# breakout_tester_1_0.net
KiCad netlist of a schematic drawn in EAGLE
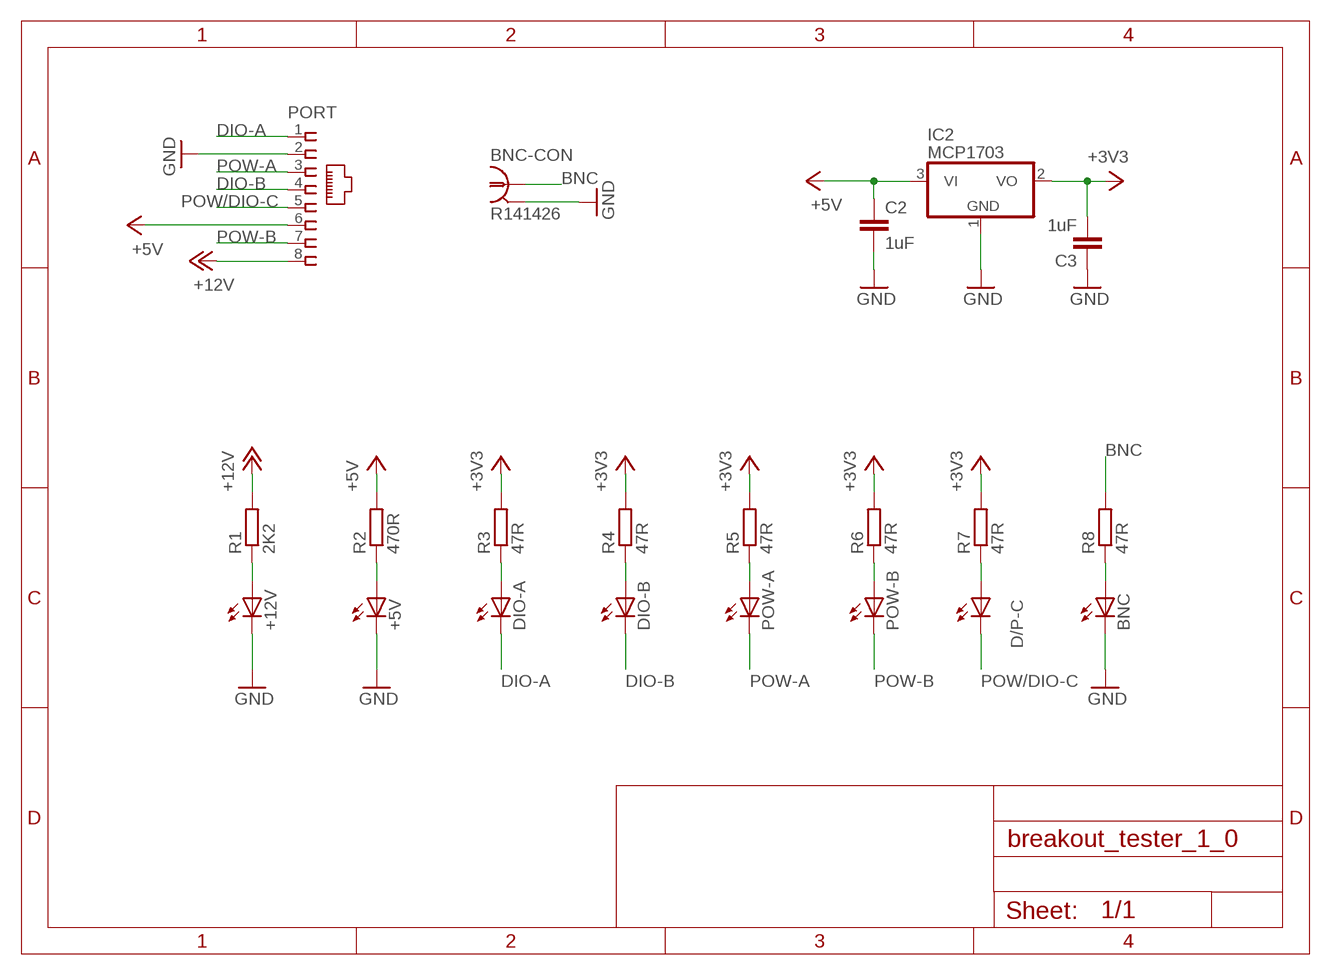
[diagram p0: schematic, sheet 1]

(export (version "E")
  (design (tool "Eeschema 10.0.6"))
  (components
    (comp (ref "+5V")
      (value "LEDSML0805")
      (footprint "eagle-import:SML0805")
      (libsource (lib "eagle-import") (part "LEDSML0805"))
    )
    (comp (ref "+12V")
      (value "LEDSML0805")
      (footprint "eagle-import:SML0805")
      (libsource (lib "eagle-import") (part "LEDSML0805"))
    )
    (comp (ref "BNC")
      (value "LEDSML0805")
      (footprint "eagle-import:SML0805")
      (libsource (lib "eagle-import") (part "LEDSML0805"))
    )
    (comp (ref "BNC-CON")
      (value "R141426")
      (footprint "eagle-import:R141426")
      (fields (field (name "MF") "FARNELL") (field (name "MPN") "R141426161"))
      (libsource (lib "eagle-import") (part "R141426"))
    )
    (comp (ref "C2")
      (value "1uF")
      (footprint "eagle-import:C0805")
      (libsource (lib "eagle-import") (part "resistor_C-EUC0805"))
    )
    (comp (ref "C3")
      (value "1uF")
      (footprint "eagle-import:C0805")
      (libsource (lib "eagle-import") (part "C-EUC0805"))
    )
    (comp (ref "D/P-C")
      (value "LEDSML0805")
      (footprint "eagle-import:SML0805")
      (libsource (lib "eagle-import") (part "LEDSML0805"))
    )
    (comp (ref "DIO-A")
      (value "LEDSML0805")
      (footprint "eagle-import:SML0805")
      (libsource (lib "eagle-import") (part "LEDSML0805"))
    )
    (comp (ref "DIO-B")
      (value "LEDSML0805")
      (footprint "eagle-import:SML0805")
      (libsource (lib "eagle-import") (part "LEDSML0805"))
    )
    (comp (ref "IC2")
      (value "MCP1703")
      (footprint "eagle-import:SOT23")
      (libsource (lib "eagle-import") (part "MCP1703CB"))
    )
    (comp (ref "PORT")
      (value "RJ45VERTICAL")
      (footprint "eagle-import:RJ45-NO-SHIELD-VERTICAL")
      (libsource (lib "eagle-import") (part "RJ45VERTICAL"))
    )
    (comp (ref "POW-A")
      (value "LEDSML0805")
      (footprint "eagle-import:SML0805")
      (libsource (lib "eagle-import") (part "LEDSML0805"))
    )
    (comp (ref "POW-B")
      (value "LEDSML0805")
      (footprint "eagle-import:SML0805")
      (libsource (lib "eagle-import") (part "LEDSML0805"))
    )
    (comp (ref "R1")
      (value "2K2")
      (footprint "eagle-import:M0805")
      (libsource (lib "eagle-import") (part "R-EU_M0805"))
    )
    (comp (ref "R2")
      (value "470R")
      (footprint "eagle-import:M0805")
      (libsource (lib "eagle-import") (part "R-EU_M0805"))
    )
    (comp (ref "R3")
      (value "47R")
      (footprint "eagle-import:M0805")
      (libsource (lib "eagle-import") (part "R-EU_M0805"))
    )
    (comp (ref "R4")
      (value "47R")
      (footprint "eagle-import:M0805")
      (libsource (lib "eagle-import") (part "R-EU_M0805"))
    )
    (comp (ref "R5")
      (value "47R")
      (footprint "eagle-import:M0805")
      (libsource (lib "eagle-import") (part "R-EU_M0805"))
    )
    (comp (ref "R6")
      (value "47R")
      (footprint "eagle-import:M0805")
      (libsource (lib "eagle-import") (part "R-EU_M0805"))
    )
    (comp (ref "R7")
      (value "47R")
      (footprint "eagle-import:M0805")
      (libsource (lib "eagle-import") (part "R-EU_M0805"))
    )
    (comp (ref "R8")
      (value "47R")
      (footprint "eagle-import:M0805")
      (libsource (lib "eagle-import") (part "R-EU_M0805"))
    )
  )
  (nets
    (net (code "1") (name "+3V3") (class "Default")
      (node (ref "C3") (pin "2") (pinfunction "2_2") (pintype "passive"))
      (node (ref "IC2") (pin "2") (pinfunction "VO_2") (pintype "passive"))
      (node (ref "R3") (pin "2") (pinfunction "2_2") (pintype "passive"))
      (node (ref "R4") (pin "2") (pinfunction "2_2") (pintype "passive"))
      (node (ref "R5") (pin "2") (pinfunction "2_2") (pintype "passive"))
      (node (ref "R6") (pin "2") (pinfunction "2_2") (pintype "passive"))
      (node (ref "R7") (pin "2") (pinfunction "2_2") (pintype "passive"))
    )
    (net (code "2") (name "+5V") (class "Default")
      (node (ref "C2") (pin "1") (pinfunction "1_1") (pintype "passive"))
      (node (ref "IC2") (pin "3") (pinfunction "VI_3") (pintype "input"))
      (node (ref "PORT") (pin "6") (pinfunction "6_6") (pintype "passive"))
      (node (ref "R2") (pin "2") (pinfunction "2_2") (pintype "passive"))
    )
    (net (code "3") (name "+12V") (class "Default")
      (node (ref "PORT") (pin "8") (pinfunction "8_8") (pintype "passive"))
      (node (ref "R1") (pin "2") (pinfunction "2_2") (pintype "passive"))
    )
    (net (code "4") (name "/BNC") (class "Default")
      (node (ref "BNC-CON") (pin "1") (pinfunction "1_1") (pintype "passive"))
      (node (ref "R8") (pin "2") (pinfunction "2_2") (pintype "passive"))
    )
    (net (code "5") (name "/DIO-A") (class "Default")
      (node (ref "DIO-A") (pin "C") (pinfunction "C_C") (pintype "passive"))
      (node (ref "PORT") (pin "1") (pinfunction "1_1") (pintype "passive"))
    )
    (net (code "6") (name "/DIO-B") (class "Default")
      (node (ref "DIO-B") (pin "C") (pinfunction "C_C") (pintype "passive"))
      (node (ref "PORT") (pin "4") (pinfunction "4_4") (pintype "passive"))
    )
    (net (code "7") (name "/POW-A") (class "Default")
      (node (ref "PORT") (pin "3") (pinfunction "3_3") (pintype "passive"))
      (node (ref "POW-A") (pin "C") (pinfunction "C_C") (pintype "passive"))
    )
    (net (code "8") (name "/POW-B") (class "Default")
      (node (ref "PORT") (pin "7") (pinfunction "7_7") (pintype "passive"))
      (node (ref "POW-B") (pin "C") (pinfunction "C_C") (pintype "passive"))
    )
    (net (code "9") (name "/POW{slash}DIO-C") (class "Default")
      (node (ref "D/P-C") (pin "C") (pinfunction "C_C") (pintype "passive"))
      (node (ref "PORT") (pin "5") (pinfunction "5_5") (pintype "passive"))
    )
    (net (code "10") (name "GND") (class "Default")
      (node (ref "+12V") (pin "C") (pinfunction "C_C") (pintype "passive"))
      (node (ref "+5V") (pin "C") (pinfunction "C_C") (pintype "passive"))
      (node (ref "BNC") (pin "C") (pinfunction "C_C") (pintype "passive"))
      (node (ref "BNC-CON") (pin "2") (pinfunction "GND_2") (pintype "power_in"))
      (node (ref "C2") (pin "2") (pinfunction "2_2") (pintype "passive"))
      (node (ref "C3") (pin "1") (pinfunction "1_1") (pintype "passive"))
      (node (ref "IC2") (pin "1") (pinfunction "GND_1") (pintype "passive"))
      (node (ref "PORT") (pin "2") (pinfunction "2_2") (pintype "passive"))
    )
    (net (code "11") (name "Net-(+5V-PadA)") (class "Default")
      (node (ref "+5V") (pin "A") (pinfunction "A_A") (pintype "passive"))
      (node (ref "R2") (pin "1") (pinfunction "1_1") (pintype "passive"))
    )
    (net (code "12") (name "Net-(+12V-PadA)") (class "Default")
      (node (ref "+12V") (pin "A") (pinfunction "A_A") (pintype "passive"))
      (node (ref "R1") (pin "1") (pinfunction "1_1") (pintype "passive"))
    )
    (net (code "13") (name "Net-(BNC-PadA)") (class "Default")
      (node (ref "BNC") (pin "A") (pinfunction "A_A") (pintype "passive"))
      (node (ref "R8") (pin "1") (pinfunction "1_1") (pintype "passive"))
    )
    (net (code "14") (name "Net-(D/P-C-PadA)") (class "Default")
      (node (ref "D/P-C") (pin "A") (pinfunction "A_A") (pintype "passive"))
      (node (ref "R7") (pin "1") (pinfunction "1_1") (pintype "passive"))
    )
    (net (code "15") (name "Net-(DIO-A-PadA)") (class "Default")
      (node (ref "DIO-A") (pin "A") (pinfunction "A_A") (pintype "passive"))
      (node (ref "R3") (pin "1") (pinfunction "1_1") (pintype "passive"))
    )
    (net (code "16") (name "Net-(DIO-B-PadA)") (class "Default")
      (node (ref "DIO-B") (pin "A") (pinfunction "A_A") (pintype "passive"))
      (node (ref "R4") (pin "1") (pinfunction "1_1") (pintype "passive"))
    )
    (net (code "17") (name "Net-(POW-A-PadA)") (class "Default")
      (node (ref "POW-A") (pin "A") (pinfunction "A_A") (pintype "passive"))
      (node (ref "R5") (pin "1") (pinfunction "1_1") (pintype "passive"))
    )
    (net (code "18") (name "Net-(POW-B-PadA)") (class "Default")
      (node (ref "POW-B") (pin "A") (pinfunction "A_A") (pintype "passive"))
      (node (ref "R6") (pin "1") (pinfunction "1_1") (pintype "passive"))
    )
  )
)
